# upper_meter.net
KiCad netlist of a schematic drawn in EAGLE
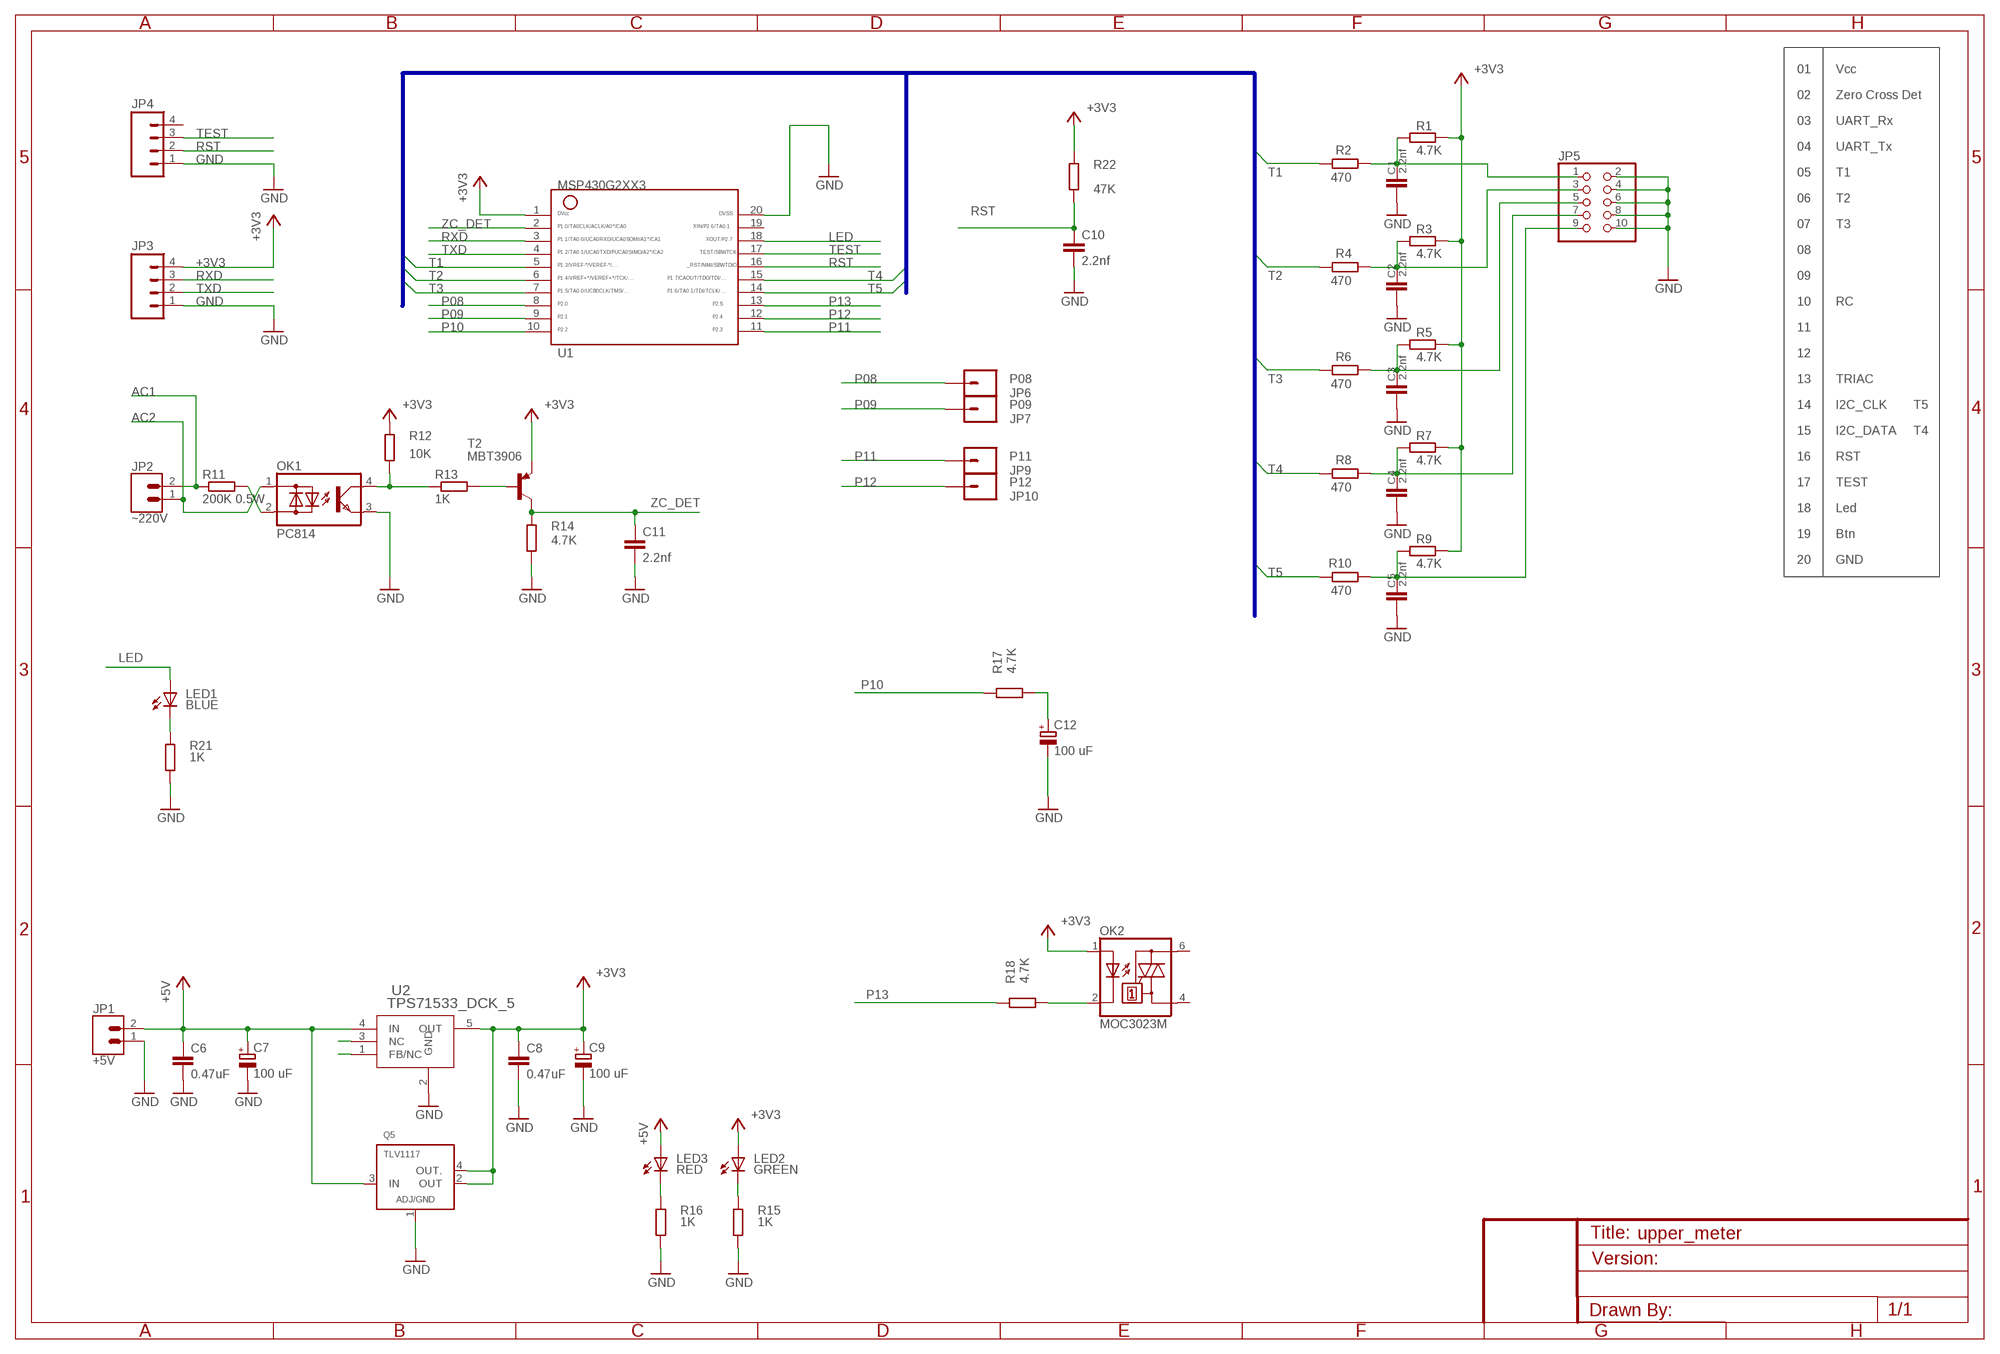
[diagram p0: schematic, sheet 1]

(export (version "E")
  (design (tool "Eeschema 10.0.6"))
  (components
    (comp (ref "C1")
      (value "2.2nf")
      (footprint "eagle-import:C0805")
      (libsource (lib "eagle-import") (part "C-EUC0805"))
    )
    (comp (ref "C2")
      (value "2.2nf")
      (footprint "eagle-import:C0805")
      (libsource (lib "eagle-import") (part "C-EUC0805"))
    )
    (comp (ref "C3")
      (value "2.2nf")
      (footprint "eagle-import:C0805")
      (libsource (lib "eagle-import") (part "C-EUC0805"))
    )
    (comp (ref "C4")
      (value "2.2nf")
      (footprint "eagle-import:C0805")
      (libsource (lib "eagle-import") (part "C-EUC0805"))
    )
    (comp (ref "C5")
      (value "2.2nf")
      (footprint "eagle-import:C0805")
      (libsource (lib "eagle-import") (part "resistor_C-EUC0805"))
    )
    (comp (ref "C6")
      (value "0.47uF")
      (footprint "eagle-import:C0805")
      (libsource (lib "eagle-import") (part "C-EUC0805"))
    )
    (comp (ref "C7")
      (value "100 uF")
      (footprint "eagle-import:E2,5-7")
      (libsource (lib "eagle-import") (part "CPOL-EUE2.5-7"))
    )
    (comp (ref "C8")
      (value "0.47uF")
      (footprint "eagle-import:C0805")
      (libsource (lib "eagle-import") (part "C-EUC0805"))
    )
    (comp (ref "C9")
      (value "100 uF")
      (footprint "eagle-import:E2,5-7")
      (libsource (lib "eagle-import") (part "CPOL-EUE2.5-7"))
    )
    (comp (ref "C10")
      (value "2.2nf")
      (footprint "eagle-import:C0805")
      (libsource (lib "eagle-import") (part "C-EUC0805"))
    )
    (comp (ref "C11")
      (value "2.2nf")
      (footprint "eagle-import:C0805")
      (libsource (lib "eagle-import") (part "C-EUC0805"))
    )
    (comp (ref "C12")
      (value "100 uF")
      (footprint "eagle-import:E2,5-7")
      (libsource (lib "eagle-import") (part "CPOL-EUE2.5-7"))
    )
    (comp (ref "JP1")
      (value "+5V")
      (footprint "eagle-import:BLUE_TERM")
      (libsource (lib "eagle-import") (part "BLUE_TERM"))
    )
    (comp (ref "JP2")
      (value "~220V")
      (footprint "eagle-import:BLUE_TERM")
      (libsource (lib "eagle-import") (part "BLUE_TERM"))
    )
    (comp (ref "JP3")
      (value "M04PTH")
      (footprint "eagle-import:1X04")
      (libsource (lib "eagle-import") (part "M04PTH"))
    )
    (comp (ref "JP4")
      (value "M04PTH")
      (footprint "eagle-import:1X04")
      (libsource (lib "eagle-import") (part "M04PTH"))
    )
    (comp (ref "JP5")
      (value "PINHD-2X5")
      (footprint "eagle-import:2X05")
      (libsource (lib "eagle-import") (part "PINHD-2X5"))
    )
    (comp (ref "JP6")
      (value "P08")
      (footprint "eagle-import:1X01")
      (libsource (lib "eagle-import") (part "M01PTH"))
    )
    (comp (ref "JP7")
      (value "P09")
      (footprint "eagle-import:1X01")
      (libsource (lib "eagle-import") (part "M01PTH"))
    )
    (comp (ref "JP9")
      (value "P11")
      (footprint "eagle-import:1X01")
      (libsource (lib "eagle-import") (part "M01PTH"))
    )
    (comp (ref "JP10")
      (value "P12")
      (footprint "eagle-import:1X01")
      (libsource (lib "eagle-import") (part "M01PTH"))
    )
    (comp (ref "LED1")
      (value "BLUE")
      (footprint "eagle-import:CHIP-LED0805")
      (libsource (lib "eagle-import") (part "LEDCHIP-LED0805"))
    )
    (comp (ref "LED2")
      (value "GREEN")
      (footprint "eagle-import:CHIP-LED0805")
      (libsource (lib "eagle-import") (part "LEDCHIP-LED0805"))
    )
    (comp (ref "LED3")
      (value "RED")
      (footprint "eagle-import:CHIP-LED0805")
      (libsource (lib "eagle-import") (part "LEDCHIP-LED0805"))
    )
    (comp (ref "OK1")
      (value "PC814")
      (footprint "eagle-import:DIL04")
      (libsource (lib "eagle-import") (part "PC814"))
    )
    (comp (ref "OK2")
      (value "MOC3023M")
      (footprint "eagle-import:DIL06")
      (fields (field (name "MF") "FAIRCHILD SEMICONDUCTOR") (field (name "MPN") "MOC3023-M"))
      (libsource (lib "eagle-import") (part "MOC30M23"))
    )
    (comp (ref "Q5")
      (value "TLV1117")
      (footprint "eagle-import:SOT223-4")
      (libsource (lib "eagle-import") (part "TLV1117"))
    )
    (comp (ref "R1")
      (value "4.7K")
      (footprint "eagle-import:R0805")
      (libsource (lib "eagle-import") (part "R-EU_R0805"))
    )
    (comp (ref "R2")
      (value "470")
      (footprint "eagle-import:R0805")
      (libsource (lib "eagle-import") (part "R-EU_R0805"))
    )
    (comp (ref "R3")
      (value "4.7K")
      (footprint "eagle-import:R0805")
      (libsource (lib "eagle-import") (part "R-EU_R0805"))
    )
    (comp (ref "R4")
      (value "470")
      (footprint "eagle-import:R0805")
      (libsource (lib "eagle-import") (part "R-EU_R0805"))
    )
    (comp (ref "R5")
      (value "4.7K")
      (footprint "eagle-import:R0805")
      (libsource (lib "eagle-import") (part "R-EU_R0805"))
    )
    (comp (ref "R6")
      (value "470")
      (footprint "eagle-import:R0805")
      (libsource (lib "eagle-import") (part "R-EU_R0805"))
    )
    (comp (ref "R7")
      (value "4.7K")
      (footprint "eagle-import:R0805")
      (libsource (lib "eagle-import") (part "R-EU_R0805"))
    )
    (comp (ref "R8")
      (value "470")
      (footprint "eagle-import:R0805")
      (libsource (lib "eagle-import") (part "R-EU_R0805"))
    )
    (comp (ref "R9")
      (value "4.7K")
      (footprint "eagle-import:R0805")
      (libsource (lib "eagle-import") (part "R-EU_R0805"))
    )
    (comp (ref "R10")
      (value "470")
      (footprint "eagle-import:R0805")
      (libsource (lib "eagle-import") (part "R-EU_R0805"))
    )
    (comp (ref "R11")
      (value "200K 0.5W")
      (footprint "eagle-import:0309_12")
      (libsource (lib "eagle-import") (part "R-EU_0309/12"))
    )
    (comp (ref "R12")
      (value "10K")
      (footprint "eagle-import:R0805")
      (libsource (lib "eagle-import") (part "R-EU_R0805"))
    )
    (comp (ref "R13")
      (value "1K")
      (footprint "eagle-import:R0805")
      (libsource (lib "eagle-import") (part "R-EU_R0805"))
    )
    (comp (ref "R14")
      (value "4.7K")
      (footprint "eagle-import:R0805")
      (libsource (lib "eagle-import") (part "R-EU_R0805"))
    )
    (comp (ref "R15")
      (value "1K")
      (footprint "eagle-import:R0805")
      (libsource (lib "eagle-import") (part "R-EU_R0805"))
    )
    (comp (ref "R16")
      (value "1K")
      (footprint "eagle-import:R0805")
      (libsource (lib "eagle-import") (part "R-EU_R0805"))
    )
    (comp (ref "R17")
      (value "4.7K")
      (footprint "eagle-import:R0805")
      (libsource (lib "eagle-import") (part "R-EU_R0805"))
    )
    (comp (ref "R18")
      (value "4.7K")
      (footprint "eagle-import:R0805")
      (libsource (lib "eagle-import") (part "R-EU_R0805"))
    )
    (comp (ref "R21")
      (value "1K")
      (footprint "eagle-import:R0805")
      (libsource (lib "eagle-import") (part "R-EU_R0805"))
    )
    (comp (ref "R22")
      (value "47K")
      (footprint "eagle-import:R0805")
      (libsource (lib "eagle-import") (part "R-EU_R0805"))
    )
    (comp (ref "T2")
      (value "MBT3906")
      (footprint "eagle-import:SOT23-BEC")
      (libsource (lib "eagle-import") (part "-PNP-SOT23-BECMMBT3906LT1"))
    )
    (comp (ref "U1")
      (value "G2XX3---PW20")
      (footprint "eagle-import:PW20")
      (libsource (lib "eagle-import") (part "G2XX3---PW20"))
    )
    (comp (ref "U2")
      (value "TPS71533_DCK_5")
      (footprint "eagle-import:DCK5")
      (fields
        (field (name "GENERIC_PART_NUMBER") "TPS71533")
        (field (name "MANUFACTURER") "Texas Instruments")
        (field (name "MANUFACTURER_PART_NUMBER") "tps71533_dck_5")
      )
      (libsource (lib "eagle-import") (part "TPS71533_DCK_5"))
    )
  )
  (nets
    (net (code "1") (name "+3V3") (class "Default")
      (node (ref "C8") (pin "1") (pinfunction "1_1") (pintype "passive"))
      (node (ref "C9") (pin "+") (pinfunction "+_+") (pintype "passive"))
      (node (ref "JP3") (pin "4") (pinfunction "4_4") (pintype "passive"))
      (node (ref "LED2") (pin "A") (pinfunction "A_A") (pintype "passive"))
      (node (ref "OK2") (pin "1") (pinfunction "A_1") (pintype "passive"))
      (node (ref "Q5") (pin "2") (pinfunction "OUT_2") (pintype "power_in"))
      (node (ref "Q5") (pin "4") (pinfunction "OUT._4") (pintype "power_in"))
      (node (ref "R1") (pin "1") (pinfunction "1_1") (pintype "passive"))
      (node (ref "R12") (pin "2") (pinfunction "2_2") (pintype "passive"))
      (node (ref "R22") (pin "2") (pinfunction "2_2") (pintype "passive"))
      (node (ref "R3") (pin "1") (pinfunction "1_1") (pintype "passive"))
      (node (ref "R5") (pin "1") (pinfunction "1_1") (pintype "passive"))
      (node (ref "R7") (pin "1") (pinfunction "1_1") (pintype "passive"))
      (node (ref "R9") (pin "1") (pinfunction "1_1") (pintype "passive"))
      (node (ref "T2") (pin "E") (pinfunction "E_E") (pintype "passive"))
      (node (ref "U1") (pin "1") (pinfunction "1_1") (pintype "bidirectional"))
      (node (ref "U2") (pin "5") (pinfunction "OUT_5") (pintype "output"))
    )
    (net (code "2") (name "+5V") (class "Default")
      (node (ref "C6") (pin "1") (pinfunction "1_1") (pintype "passive"))
      (node (ref "C7") (pin "+") (pinfunction "+_+") (pintype "passive"))
      (node (ref "JP1") (pin "2") (pinfunction "2_2") (pintype "passive"))
      (node (ref "LED3") (pin "A") (pinfunction "A_A") (pintype "passive"))
      (node (ref "Q5") (pin "3") (pinfunction "IN_3") (pintype "power_in"))
      (node (ref "U2") (pin "4") (pinfunction "IN_4") (pintype "input"))
    )
    (net (code "3") (name "/AC1") (class "Default")
      (node (ref "JP2") (pin "2") (pinfunction "2_2") (pintype "passive"))
      (node (ref "R11") (pin "1") (pinfunction "1_1") (pintype "passive"))
    )
    (net (code "4") (name "/AC2") (class "Default")
      (node (ref "JP2") (pin "1") (pinfunction "1_1") (pintype "passive"))
      (node (ref "OK1") (pin "1") (pinfunction "AC1_1") (pintype "passive"))
    )
    (net (code "5") (name "/LED") (class "Default")
      (node (ref "LED1") (pin "A") (pinfunction "A_A") (pintype "passive"))
      (node (ref "U1") (pin "18") (pinfunction "18_18") (pintype "bidirectional"))
    )
    (net (code "6") (name "/P08") (class "Default")
      (node (ref "JP6") (pin "1") (pinfunction "1_1") (pintype "passive"))
      (node (ref "U1") (pin "8") (pinfunction "8_8") (pintype "bidirectional"))
    )
    (net (code "7") (name "/P09") (class "Default")
      (node (ref "JP7") (pin "1") (pinfunction "1_1") (pintype "passive"))
      (node (ref "U1") (pin "9") (pinfunction "9_9") (pintype "bidirectional"))
    )
    (net (code "8") (name "/P10") (class "Default")
      (node (ref "R17") (pin "2") (pinfunction "2_2") (pintype "passive"))
      (node (ref "U1") (pin "10") (pinfunction "10_10") (pintype "bidirectional"))
    )
    (net (code "9") (name "/P11") (class "Default")
      (node (ref "JP9") (pin "1") (pinfunction "1_1") (pintype "passive"))
      (node (ref "U1") (pin "11") (pinfunction "11_11") (pintype "bidirectional"))
    )
    (net (code "10") (name "/P12") (class "Default")
      (node (ref "JP10") (pin "1") (pinfunction "1_1") (pintype "passive"))
      (node (ref "U1") (pin "12") (pinfunction "12_12") (pintype "bidirectional"))
    )
    (net (code "11") (name "/P13") (class "Default")
      (node (ref "R18") (pin "2") (pinfunction "2_2") (pintype "passive"))
      (node (ref "U1") (pin "13") (pinfunction "13_13") (pintype "bidirectional"))
    )
    (net (code "12") (name "/RST") (class "Default")
      (node (ref "C10") (pin "1") (pinfunction "1_1") (pintype "passive"))
      (node (ref "JP4") (pin "2") (pinfunction "2_2") (pintype "passive"))
      (node (ref "R22") (pin "1") (pinfunction "1_1") (pintype "passive"))
      (node (ref "U1") (pin "16") (pinfunction "16_16") (pintype "bidirectional"))
    )
    (net (code "13") (name "/RXD") (class "Default")
      (node (ref "JP3") (pin "3") (pinfunction "3_3") (pintype "passive"))
      (node (ref "U1") (pin "3") (pinfunction "3_3") (pintype "bidirectional"))
    )
    (net (code "14") (name "/T1") (class "Default")
      (node (ref "R2") (pin "1") (pinfunction "1_1") (pintype "passive"))
      (node (ref "U1") (pin "5") (pinfunction "5_5") (pintype "bidirectional"))
    )
    (net (code "15") (name "/T2") (class "Default")
      (node (ref "R4") (pin "1") (pinfunction "1_1") (pintype "passive"))
      (node (ref "U1") (pin "6") (pinfunction "6_6") (pintype "bidirectional"))
    )
    (net (code "16") (name "/T3") (class "Default")
      (node (ref "R6") (pin "1") (pinfunction "1_1") (pintype "passive"))
      (node (ref "U1") (pin "7") (pinfunction "7_7") (pintype "bidirectional"))
    )
    (net (code "17") (name "/T4") (class "Default")
      (node (ref "R8") (pin "1") (pinfunction "1_1") (pintype "passive"))
      (node (ref "U1") (pin "15") (pinfunction "15_15") (pintype "bidirectional"))
    )
    (net (code "18") (name "/T5") (class "Default")
      (node (ref "R10") (pin "1") (pinfunction "1_1") (pintype "passive"))
      (node (ref "U1") (pin "14") (pinfunction "14_14") (pintype "bidirectional"))
    )
    (net (code "19") (name "/TEST") (class "Default")
      (node (ref "JP4") (pin "3") (pinfunction "3_3") (pintype "passive"))
      (node (ref "U1") (pin "17") (pinfunction "17_17") (pintype "bidirectional"))
    )
    (net (code "20") (name "/TXD") (class "Default")
      (node (ref "JP3") (pin "2") (pinfunction "2_2") (pintype "passive"))
      (node (ref "U1") (pin "4") (pinfunction "4_4") (pintype "bidirectional"))
    )
    (net (code "21") (name "/ZC_DET") (class "Default")
      (node (ref "C11") (pin "1") (pinfunction "1_1") (pintype "passive"))
      (node (ref "R14") (pin "2") (pinfunction "2_2") (pintype "passive"))
      (node (ref "T2") (pin "C") (pinfunction "C_C") (pintype "passive"))
      (node (ref "U1") (pin "2") (pinfunction "2_2") (pintype "bidirectional"))
    )
    (net (code "22") (name "GND") (class "Default")
      (node (ref "C1") (pin "1") (pinfunction "1_1") (pintype "passive"))
      (node (ref "C10") (pin "2") (pinfunction "2_2") (pintype "passive"))
      (node (ref "C11") (pin "2") (pinfunction "2_2") (pintype "passive"))
      (node (ref "C12") (pin "-") (pinfunction "-_-") (pintype "passive"))
      (node (ref "C2") (pin "1") (pinfunction "1_1") (pintype "passive"))
      (node (ref "C3") (pin "1") (pinfunction "1_1") (pintype "passive"))
      (node (ref "C4") (pin "1") (pinfunction "1_1") (pintype "passive"))
      (node (ref "C5") (pin "1") (pinfunction "1_1") (pintype "passive"))
      (node (ref "C6") (pin "2") (pinfunction "2_2") (pintype "passive"))
      (node (ref "C7") (pin "-") (pinfunction "-_-") (pintype "passive"))
      (node (ref "C8") (pin "2") (pinfunction "2_2") (pintype "passive"))
      (node (ref "C9") (pin "-") (pinfunction "-_-") (pintype "passive"))
      (node (ref "JP1") (pin "1") (pinfunction "1_1") (pintype "passive"))
      (node (ref "JP3") (pin "1") (pinfunction "1_1") (pintype "passive"))
      (node (ref "JP4") (pin "1") (pinfunction "1_1") (pintype "passive"))
      (node (ref "JP5") (pin "10") (pinfunction "10_10") (pintype "passive"))
      (node (ref "JP5") (pin "2") (pinfunction "2_2") (pintype "passive"))
      (node (ref "JP5") (pin "4") (pinfunction "4_4") (pintype "passive"))
      (node (ref "JP5") (pin "6") (pinfunction "6_6") (pintype "passive"))
      (node (ref "JP5") (pin "8") (pinfunction "8_8") (pintype "passive"))
      (node (ref "OK1") (pin "3") (pinfunction "E_3") (pintype "passive"))
      (node (ref "Q5") (pin "1") (pinfunction "ADJ/GND_1") (pintype "bidirectional"))
      (node (ref "R14") (pin "1") (pinfunction "1_1") (pintype "passive"))
      (node (ref "R15") (pin "1") (pinfunction "1_1") (pintype "passive"))
      (node (ref "R16") (pin "1") (pinfunction "1_1") (pintype "passive"))
      (node (ref "R21") (pin "1") (pinfunction "1_1") (pintype "passive"))
      (node (ref "U1") (pin "20") (pinfunction "20_20") (pintype "bidirectional"))
      (node (ref "U2") (pin "2") (pinfunction "GND_2") (pintype "power_in"))
    )
    (net (code "23") (name "Net-(C1-Pad2)") (class "Default")
      (node (ref "C1") (pin "2") (pinfunction "2_2") (pintype "passive"))
      (node (ref "JP5") (pin "1") (pinfunction "1_1") (pintype "passive"))
      (node (ref "R1") (pin "2") (pinfunction "2_2") (pintype "passive"))
      (node (ref "R2") (pin "2") (pinfunction "2_2") (pintype "passive"))
    )
    (net (code "24") (name "Net-(C2-Pad2)") (class "Default")
      (node (ref "C2") (pin "2") (pinfunction "2_2") (pintype "passive"))
      (node (ref "JP5") (pin "3") (pinfunction "3_3") (pintype "passive"))
      (node (ref "R3") (pin "2") (pinfunction "2_2") (pintype "passive"))
      (node (ref "R4") (pin "2") (pinfunction "2_2") (pintype "passive"))
    )
    (net (code "25") (name "Net-(C3-Pad2)") (class "Default")
      (node (ref "C3") (pin "2") (pinfunction "2_2") (pintype "passive"))
      (node (ref "JP5") (pin "5") (pinfunction "5_5") (pintype "passive"))
      (node (ref "R5") (pin "2") (pinfunction "2_2") (pintype "passive"))
      (node (ref "R6") (pin "2") (pinfunction "2_2") (pintype "passive"))
    )
    (net (code "26") (name "Net-(C4-Pad2)") (class "Default")
      (node (ref "C4") (pin "2") (pinfunction "2_2") (pintype "passive"))
      (node (ref "JP5") (pin "7") (pinfunction "7_7") (pintype "passive"))
      (node (ref "R7") (pin "2") (pinfunction "2_2") (pintype "passive"))
      (node (ref "R8") (pin "2") (pinfunction "2_2") (pintype "passive"))
    )
    (net (code "27") (name "Net-(C5-Pad2)") (class "Default")
      (node (ref "C5") (pin "2") (pinfunction "2_2") (pintype "passive"))
      (node (ref "JP5") (pin "9") (pinfunction "9_9") (pintype "passive"))
      (node (ref "R10") (pin "2") (pinfunction "2_2") (pintype "passive"))
      (node (ref "R9") (pin "2") (pinfunction "2_2") (pintype "passive"))
    )
    (net (code "28") (name "Net-(C12-Pad+)") (class "Default")
      (node (ref "C12") (pin "+") (pinfunction "+_+") (pintype "passive"))
      (node (ref "R17") (pin "1") (pinfunction "1_1") (pintype "passive"))
    )
    (net (code "29") (name "Net-(LED1-PadC)") (class "Default")
      (node (ref "LED1") (pin "C") (pinfunction "C_C") (pintype "passive"))
      (node (ref "R21") (pin "2") (pinfunction "2_2") (pintype "passive"))
    )
    (net (code "30") (name "Net-(LED2-PadC)") (class "Default")
      (node (ref "LED2") (pin "C") (pinfunction "C_C") (pintype "passive"))
      (node (ref "R15") (pin "2") (pinfunction "2_2") (pintype "passive"))
    )
    (net (code "31") (name "Net-(LED3-PadC)") (class "Default")
      (node (ref "LED3") (pin "C") (pinfunction "C_C") (pintype "passive"))
      (node (ref "R16") (pin "2") (pinfunction "2_2") (pintype "passive"))
    )
    (net (code "32") (name "Net-(OK1-AC2)") (class "Default")
      (node (ref "OK1") (pin "2") (pinfunction "AC2_2") (pintype "passive"))
      (node (ref "R11") (pin "2") (pinfunction "2_2") (pintype "passive"))
    )
    (net (code "33") (name "Net-(OK1-C)") (class "Default")
      (node (ref "OK1") (pin "4") (pinfunction "C_4") (pintype "passive"))
      (node (ref "R12") (pin "1") (pinfunction "1_1") (pintype "passive"))
      (node (ref "R13") (pin "1") (pinfunction "1_1") (pintype "passive"))
    )
    (net (code "34") (name "Net-(OK2-C)") (class "Default")
      (node (ref "OK2") (pin "2") (pinfunction "C_2") (pintype "passive"))
      (node (ref "R18") (pin "1") (pinfunction "1_1") (pintype "passive"))
    )
    (net (code "35") (name "Net-(R13-Pad2)") (class "Default")
      (node (ref "R13") (pin "2") (pinfunction "2_2") (pintype "passive"))
      (node (ref "T2") (pin "B") (pinfunction "B_B") (pintype "passive"))
    )
    (net (code "36") (name "unconnected-(JP4-Pad4)") (class "Default")
      (node (ref "JP4") (pin "4") (pinfunction "4_4") (pintype "passive"))
    )
    (net (code "37") (name "unconnected-(OK2-A1-Pad4)") (class "Default")
      (node (ref "OK2") (pin "4") (pinfunction "A1_4") (pintype "passive"))
    )
    (net (code "38") (name "unconnected-(OK2-A2-Pad6)") (class "Default")
      (node (ref "OK2") (pin "6") (pinfunction "A2_6") (pintype "passive"))
    )
    (net (code "39") (name "unconnected-(U1-Pad19)") (class "Default")
      (node (ref "U1") (pin "19") (pinfunction "19_19") (pintype "bidirectional"))
    )
    (net (code "40") (name "unconnected-(U2-FB{slash}NC-Pad1)") (class "Default")
      (node (ref "U2") (pin "1") (pinfunction "FB/NC_1") (pintype "bidirectional"))
    )
    (net (code "41") (name "unconnected-(U2-NC-Pad3)") (class "Default")
      (node (ref "U2") (pin "3") (pinfunction "NC_3") (pintype "passive"))
    )
  )
)
